# cc2538-dev-v1.net
KiCad netlist of a schematic drawn in EAGLE
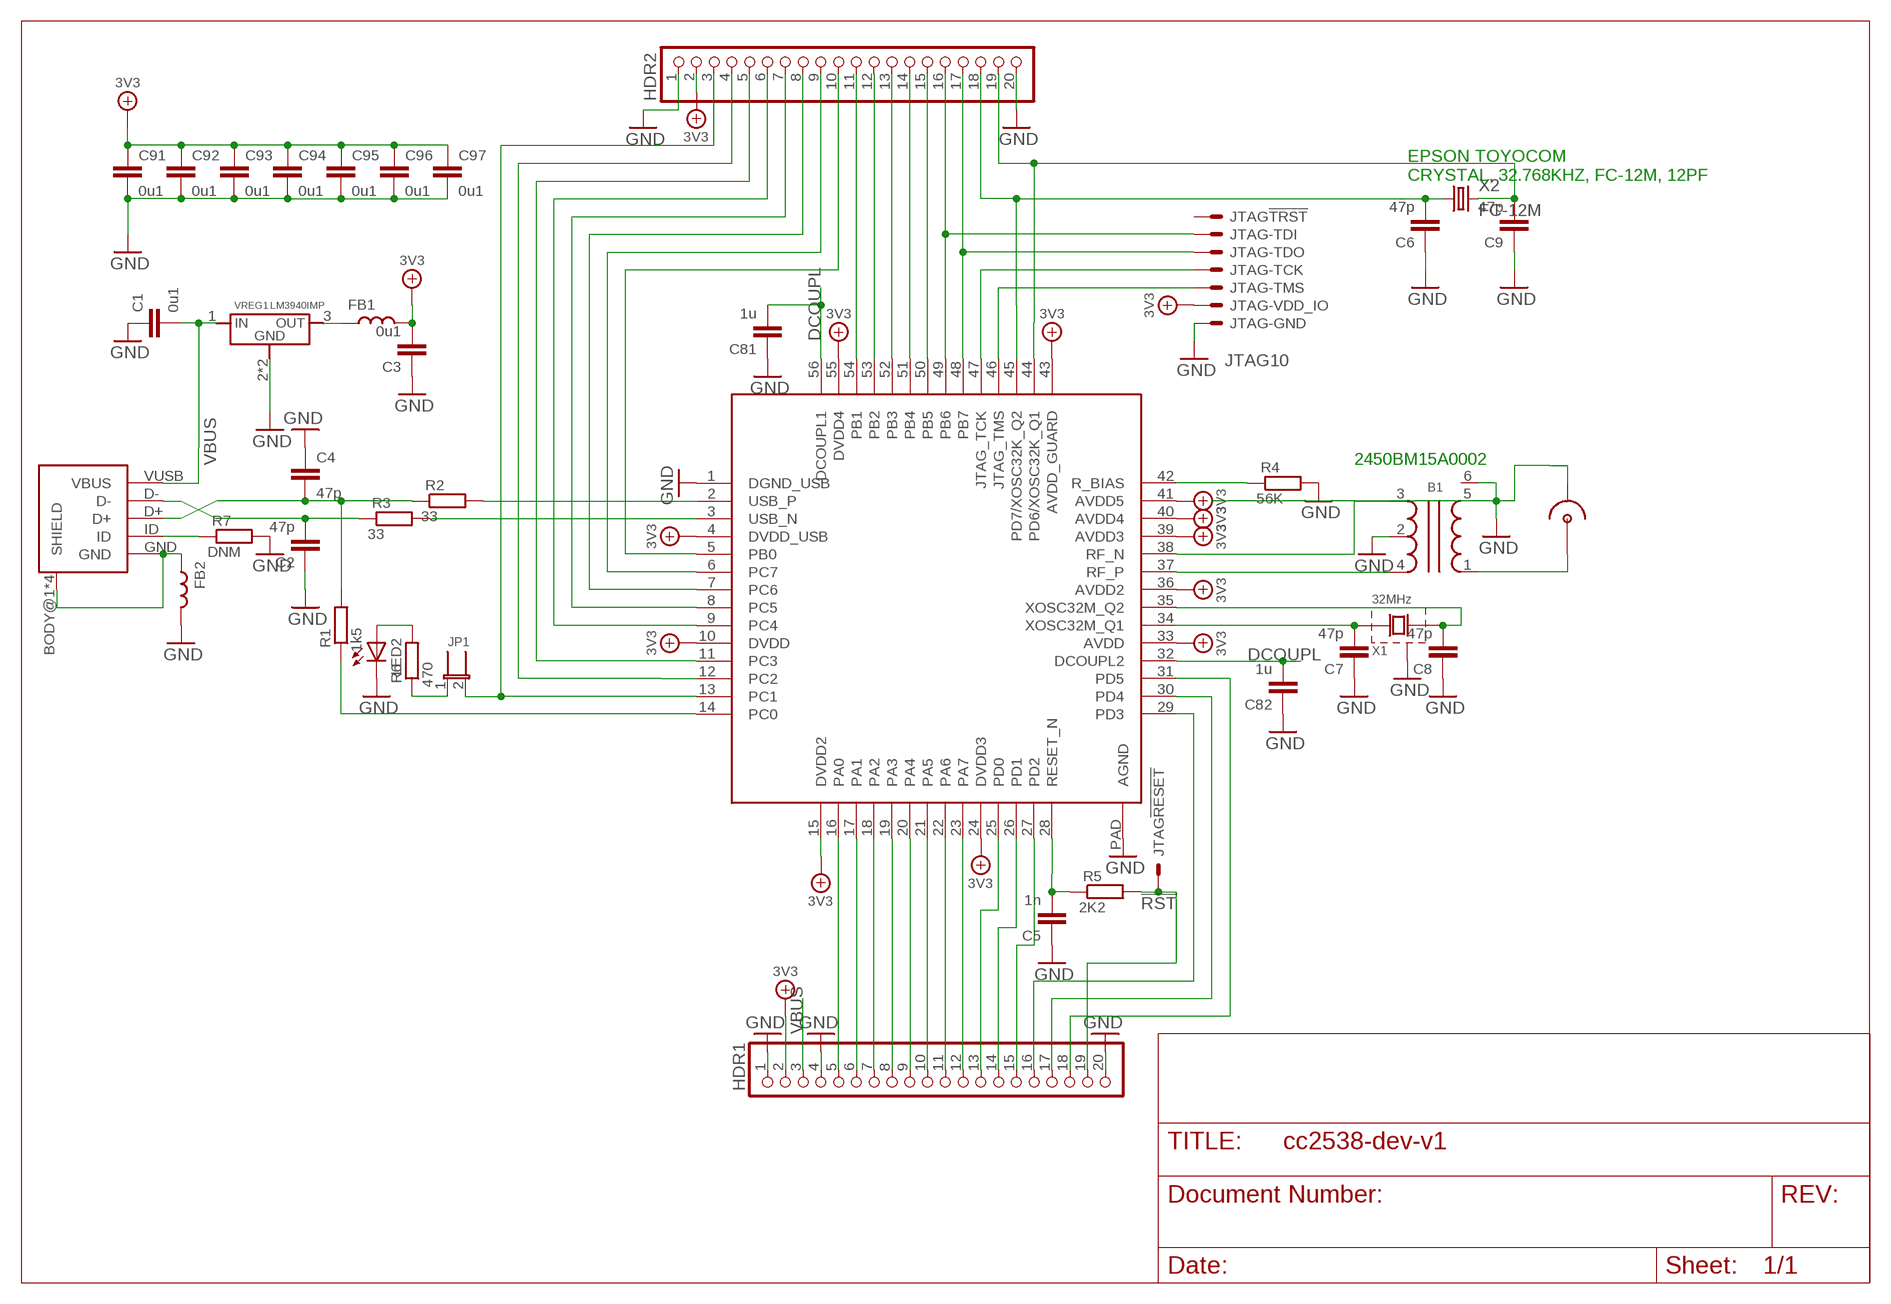
[diagram p0: schematic, sheet 1]

(export (version "E")
  (design (tool "Eeschema 10.0.6"))
  (components
    (comp (ref "B1")
      (value "BALUN")
      (footprint "eagle-import:BALUN-0805")
      (libsource (lib "eagle-import") (part "BALUN"))
    )
    (comp (ref "C1")
      (value "0u1")
      (footprint "eagle-import:C1206")
      (libsource (lib "eagle-import") (part "CC1206"))
    )
    (comp (ref "C2")
      (value "47p")
      (footprint "eagle-import:C0603")
      (libsource (lib "eagle-import") (part "CC0603"))
    )
    (comp (ref "C3")
      (value "0u1")
      (footprint "eagle-import:C1206")
      (libsource (lib "eagle-import") (part "CC1206"))
    )
    (comp (ref "C4")
      (value "47p")
      (footprint "eagle-import:C0603")
      (libsource (lib "eagle-import") (part "CC0603"))
    )
    (comp (ref "C5")
      (value "1n")
      (footprint "eagle-import:C0603")
      (libsource (lib "eagle-import") (part "CC0603"))
    )
    (comp (ref "C6")
      (value "47p")
      (footprint "eagle-import:C0603")
      (libsource (lib "eagle-import") (part "CC0603"))
    )
    (comp (ref "C7")
      (value "47p")
      (footprint "eagle-import:C0603")
      (libsource (lib "eagle-import") (part "CC0603"))
    )
    (comp (ref "C8")
      (value "47p")
      (footprint "eagle-import:C0603")
      (libsource (lib "eagle-import") (part "CC0603"))
    )
    (comp (ref "C9")
      (value "47p")
      (footprint "eagle-import:C0603")
      (libsource (lib "eagle-import") (part "CC0603"))
    )
    (comp (ref "C81")
      (value "1u")
      (footprint "eagle-import:C0402")
      (libsource (lib "eagle-import") (part "CC0402"))
    )
    (comp (ref "C82")
      (value "1u")
      (footprint "eagle-import:C0402")
      (libsource (lib "eagle-import") (part "CC0402"))
    )
    (comp (ref "C91")
      (value "0u1")
      (footprint "eagle-import:C0402")
      (libsource (lib "eagle-import") (part "CC0402"))
    )
    (comp (ref "C92")
      (value "0u1")
      (footprint "eagle-import:C0402")
      (libsource (lib "eagle-import") (part "CC0402"))
    )
    (comp (ref "C93")
      (value "0u1")
      (footprint "eagle-import:C0402")
      (libsource (lib "eagle-import") (part "CC0402"))
    )
    (comp (ref "C94")
      (value "0u1")
      (footprint "eagle-import:C0402")
      (libsource (lib "eagle-import") (part "CC0402"))
    )
    (comp (ref "C95")
      (value "0u1")
      (footprint "eagle-import:C0402")
      (libsource (lib "eagle-import") (part "CC0402"))
    )
    (comp (ref "C96")
      (value "0u1")
      (footprint "eagle-import:C0402")
      (libsource (lib "eagle-import") (part "CC0402"))
    )
    (comp (ref "C97")
      (value "0u1")
      (footprint "eagle-import:C0402")
      (libsource (lib "eagle-import") (part "CC0402"))
    )
    (comp (ref "CN1")
      (value "USB-OTG")
      (footprint "eagle-import:CONN_USB_MINI-B")
      (libsource (lib "eagle-import") (part "USB-OTG"))
    )
    (comp (ref "CN2")
      (value "RF-CONNSMA")
      (footprint "eagle-import:SMA")
      (libsource (lib "eagle-import") (part "RF-CONNSMA"))
    )
    (comp (ref "FB1")
      (value "L0603")
      (footprint "eagle-import:R603")
      (libsource (lib "eagle-import") (part "L0603"))
    )
    (comp (ref "FB2")
      (value "L0603")
      (footprint "eagle-import:R603")
      (libsource (lib "eagle-import") (part "L0603"))
    )
    (comp (ref "HDR1")
      (value "PINHD-1X20")
      (footprint "eagle-import:1X20")
      (libsource (lib "eagle-import") (part "PINHD-1X20"))
    )
    (comp (ref "HDR2")
      (value "PINHD-1X20")
      (footprint "eagle-import:1X20")
      (libsource (lib "eagle-import") (part "PINHD-1X20"))
    )
    (comp (ref "JP1")
      (value "JP-2MM-2")
      (footprint "eagle-import:JP-2MM-2")
      (libsource (lib "eagle-import") (part "JP-2MM-2"))
    )
    (comp (ref "JTAG")
      (value "JTAG10")
      (footprint "eagle-import:HDR-2X5-2.00")
      (libsource (lib "eagle-import") (part "JTAG10"))
    )
    (comp (ref "LED2")
      (value "LED805")
      (footprint "eagle-import:LED-805")
      (libsource (lib "eagle-import") (part "LED805"))
    )
    (comp (ref "R1")
      (value "1k5")
      (footprint "eagle-import:R603")
      (libsource (lib "eagle-import") (part "RR603"))
    )
    (comp (ref "R2")
      (value "33")
      (footprint "eagle-import:R603")
      (libsource (lib "eagle-import") (part "RR603"))
    )
    (comp (ref "R3")
      (value "33")
      (footprint "eagle-import:R603")
      (libsource (lib "eagle-import") (part "RR603"))
    )
    (comp (ref "R4")
      (value "56K")
      (footprint "eagle-import:R603")
      (libsource (lib "eagle-import") (part "RR603"))
    )
    (comp (ref "R5")
      (value "2K2")
      (footprint "eagle-import:R603")
      (libsource (lib "eagle-import") (part "RR603"))
    )
    (comp (ref "R6")
      (value "470")
      (footprint "eagle-import:R603")
      (libsource (lib "eagle-import") (part "RR603"))
    )
    (comp (ref "R7")
      (value "DNM")
      (footprint "eagle-import:R603")
      (libsource (lib "eagle-import") (part "RR603"))
    )
    (comp (ref "U1")
      (value "CC2538")
      (footprint "eagle-import:QFN56")
      (libsource (lib "eagle-import") (part "CC2538"))
    )
    (comp (ref "VREG1")
      (value "LM3940IMP")
      (footprint "eagle-import:SOT223")
      (libsource (lib "eagle-import") (part "LM3940IMP"))
    )
    (comp (ref "X1")
      (value "32MHz")
      (footprint "eagle-import:XTAL-4-3225")
      (libsource (lib "eagle-import") (part "XTAL-43225"))
    )
    (comp (ref "X2")
      (value "FC-12M")
      (footprint "eagle-import:FC-12M")
      (libsource (lib "eagle-import") (part "FC-12M"))
    )
  )
  (nets
    (net (code "1") (name "/DCOUPL") (class "Default")
      (node (ref "C81") (pin "2") (pinfunction "2_2") (pintype "passive"))
      (node (ref "C82") (pin "2") (pinfunction "2_2") (pintype "passive"))
      (node (ref "U1") (pin "32") (pinfunction "DCOUPL2_32") (pintype "bidirectional"))
      (node (ref "U1") (pin "56") (pinfunction "DCOUPL1_56") (pintype "bidirectional"))
    )
    (net (code "2") (name "/VBUS") (class "Default")
      (node (ref "C1") (pin "2") (pinfunction "2_2") (pintype "passive"))
      (node (ref "CN1") (pin "VUSB") (pinfunction "VBUS_VUSB") (pintype "bidirectional"))
      (node (ref "HDR1") (pin "3") (pinfunction "3_3") (pintype "passive"))
      (node (ref "VREG1") (pin "1") (pinfunction "IN_1") (pintype "bidirectional"))
    )
    (net (code "3") (name "/~{RST}") (class "Default")
      (node (ref "HDR1") (pin "19") (pinfunction "19_19") (pintype "passive"))
      (node (ref "JTAG") (pin "4") (pinfunction "S_4") (pintype "passive"))
      (node (ref "R5") (pin "2") (pinfunction "2_2") (pintype "passive"))
    )
    (net (code "4") (name "3V3") (class "Default")
      (node (ref "C3") (pin "2") (pinfunction "2_2") (pintype "passive"))
      (node (ref "C91") (pin "1") (pinfunction "1_1") (pintype "passive"))
      (node (ref "C92") (pin "1") (pinfunction "1_1") (pintype "passive"))
      (node (ref "C93") (pin "1") (pinfunction "1_1") (pintype "passive"))
      (node (ref "C94") (pin "1") (pinfunction "1_1") (pintype "passive"))
      (node (ref "C95") (pin "1") (pinfunction "1_1") (pintype "passive"))
      (node (ref "C96") (pin "1") (pinfunction "1_1") (pintype "passive"))
      (node (ref "C97") (pin "1") (pinfunction "1_1") (pintype "passive"))
      (node (ref "FB1") (pin "2") (pinfunction "P$2_2") (pintype "bidirectional"))
      (node (ref "HDR1") (pin "2") (pinfunction "2_2") (pintype "passive"))
      (node (ref "HDR2") (pin "2") (pinfunction "2_2") (pintype "passive"))
      (node (ref "JTAG") (pin "1") (pinfunction "S_1") (pintype "passive"))
      (node (ref "JTAG") (pin "2") (pinfunction "S_2") (pintype "passive"))
      (node (ref "U1") (pin "10") (pinfunction "DVDD_10") (pintype "bidirectional"))
      (node (ref "U1") (pin "15") (pinfunction "DVDD2_15") (pintype "bidirectional"))
      (node (ref "U1") (pin "24") (pinfunction "DVDD3_24") (pintype "bidirectional"))
      (node (ref "U1") (pin "33") (pinfunction "AVDD_33") (pintype "bidirectional"))
      (node (ref "U1") (pin "36") (pinfunction "AVDD2_36") (pintype "bidirectional"))
      (node (ref "U1") (pin "39") (pinfunction "AVDD3_39") (pintype "bidirectional"))
      (node (ref "U1") (pin "4") (pinfunction "DVDD_USB_4") (pintype "bidirectional"))
      (node (ref "U1") (pin "40") (pinfunction "AVDD4_40") (pintype "bidirectional"))
      (node (ref "U1") (pin "41") (pinfunction "AVDD5_41") (pintype "bidirectional"))
      (node (ref "U1") (pin "43") (pinfunction "AVDD_GUARD_43") (pintype "bidirectional"))
      (node (ref "U1") (pin "55") (pinfunction "DVDD4_55") (pintype "bidirectional"))
    )
    (net (code "5") (name "GND") (class "Default")
      (node (ref "B1") (pin "2") (pinfunction "2_2") (pintype "bidirectional"))
      (node (ref "B1") (pin "5") (pinfunction "5_5") (pintype "bidirectional"))
      (node (ref "B1") (pin "6") (pinfunction "6_6") (pintype "bidirectional"))
      (node (ref "C1") (pin "1") (pinfunction "1_1") (pintype "passive"))
      (node (ref "C2") (pin "1") (pinfunction "1_1") (pintype "passive"))
      (node (ref "C3") (pin "1") (pinfunction "1_1") (pintype "passive"))
      (node (ref "C4") (pin "1") (pinfunction "1_1") (pintype "passive"))
      (node (ref "C5") (pin "1") (pinfunction "1_1") (pintype "passive"))
      (node (ref "C6") (pin "1") (pinfunction "1_1") (pintype "passive"))
      (node (ref "C7") (pin "1") (pinfunction "1_1") (pintype "passive"))
      (node (ref "C8") (pin "1") (pinfunction "1_1") (pintype "passive"))
      (node (ref "C81") (pin "1") (pinfunction "1_1") (pintype "passive"))
      (node (ref "C82") (pin "1") (pinfunction "1_1") (pintype "passive"))
      (node (ref "C9") (pin "1") (pinfunction "1_1") (pintype "passive"))
      (node (ref "C91") (pin "2") (pinfunction "2_2") (pintype "passive"))
      (node (ref "C92") (pin "2") (pinfunction "2_2") (pintype "passive"))
      (node (ref "C93") (pin "2") (pinfunction "2_2") (pintype "passive"))
      (node (ref "C94") (pin "2") (pinfunction "2_2") (pintype "passive"))
      (node (ref "C95") (pin "2") (pinfunction "2_2") (pintype "passive"))
      (node (ref "C96") (pin "2") (pinfunction "2_2") (pintype "passive"))
      (node (ref "C97") (pin "2") (pinfunction "2_2") (pintype "passive"))
      (node (ref "CN2") (pin "GND1") (pinfunction "GND_GND1") (pintype "bidirectional"))
      (node (ref "CN2") (pin "GND2") (pinfunction "GND_GND2") (pintype "bidirectional"))
      (node (ref "CN2") (pin "GND3") (pinfunction "GND_GND3") (pintype "bidirectional"))
      (node (ref "CN2") (pin "GND4") (pinfunction "GND_GND4") (pintype "bidirectional"))
      (node (ref "FB2") (pin "2") (pinfunction "P$2_2") (pintype "bidirectional"))
      (node (ref "HDR1") (pin "1") (pinfunction "1_1") (pintype "passive"))
      (node (ref "HDR1") (pin "20") (pinfunction "20_20") (pintype "passive"))
      (node (ref "HDR1") (pin "4") (pinfunction "4_4") (pintype "passive"))
      (node (ref "HDR2") (pin "1") (pinfunction "1_1") (pintype "passive"))
      (node (ref "HDR2") (pin "20") (pinfunction "20_20") (pintype "passive"))
      (node (ref "JTAG") (pin "10") (pinfunction "S_10") (pintype "passive"))
      (node (ref "JTAG") (pin "8") (pinfunction "S_8") (pintype "passive"))
      (node (ref "LED2") (pin "C") (pinfunction "C_C") (pintype "passive"))
      (node (ref "R4") (pin "2") (pinfunction "2_2") (pintype "passive"))
      (node (ref "R7") (pin "2") (pinfunction "2_2") (pintype "passive"))
      (node (ref "U1") (pin "1") (pinfunction "DGND_USB_1") (pintype "bidirectional"))
      (node (ref "U1") (pin "PAD") (pinfunction "AGND_PAD") (pintype "bidirectional"))
      (node (ref "VREG1") (pin "2") (pinfunction "GND_2") (pintype "bidirectional"))
      (node (ref "VREG1") (pin "4") (pinfunction "GND_4") (pintype "bidirectional"))
      (node (ref "X1") (pin "2") (pinfunction "GND1_2") (pintype "bidirectional"))
      (node (ref "X1") (pin "4") (pinfunction "GND1_4") (pintype "bidirectional"))
    )
    (net (code "6") (name "Net-(C2-Pad2)") (class "Default")
      (node (ref "C2") (pin "2") (pinfunction "2_2") (pintype "passive"))
      (node (ref "CN1") (pin "D-") (pinfunction "D-_D-") (pintype "bidirectional"))
      (node (ref "R3") (pin "1") (pinfunction "1_1") (pintype "passive"))
    )
    (net (code "7") (name "Net-(C4-Pad2)") (class "Default")
      (node (ref "C4") (pin "2") (pinfunction "2_2") (pintype "passive"))
      (node (ref "CN1") (pin "D+") (pinfunction "D+_D+") (pintype "bidirectional"))
      (node (ref "R1") (pin "2") (pinfunction "2_2") (pintype "passive"))
      (node (ref "R2") (pin "1") (pinfunction "1_1") (pintype "passive"))
    )
    (net (code "8") (name "Net-(CN1-PadID)") (class "Default")
      (node (ref "CN1") (pin "ID") (pinfunction "ID_ID") (pintype "bidirectional"))
      (node (ref "R7") (pin "1") (pinfunction "1_1") (pintype "passive"))
    )
    (net (code "9") (name "Net-(CN2-SIGNAL)") (class "Default")
      (node (ref "B1") (pin "1") (pinfunction "1_1") (pintype "bidirectional"))
      (node (ref "CN2") (pin "SIG") (pinfunction "SIGNAL_SIG") (pintype "bidirectional"))
    )
    (net (code "10") (name "Net-(FB1-P$1)") (class "Default")
      (node (ref "FB1") (pin "1") (pinfunction "P$1_1") (pintype "bidirectional"))
      (node (ref "VREG1") (pin "3") (pinfunction "OUT_3") (pintype "bidirectional"))
    )
    (net (code "11") (name "Net-(FB2-P$1)") (class "Default")
      (node (ref "CN1") (pin "BODY@1") (pinfunction "SHIELD_BODY@1") (pintype "bidirectional"))
      (node (ref "CN1") (pin "BODY@2") (pinfunction "SHIELD_BODY@2") (pintype "bidirectional"))
      (node (ref "CN1") (pin "BODY@3") (pinfunction "SHIELD_BODY@3") (pintype "bidirectional"))
      (node (ref "CN1") (pin "BODY@4") (pinfunction "SHIELD_BODY@4") (pintype "bidirectional"))
      (node (ref "CN1") (pin "GND") (pinfunction "GND_GND") (pintype "bidirectional"))
      (node (ref "FB2") (pin "1") (pinfunction "P$1_1") (pintype "bidirectional"))
    )
    (net (code "12") (name "Net-(JP1-Pad1)") (class "Default")
      (node (ref "JP1") (pin "1") (pinfunction "1_1") (pintype "bidirectional"))
      (node (ref "R6") (pin "1") (pinfunction "1_1") (pintype "passive"))
    )
    (net (code "13") (name "Net-(JTAGD-S)") (class "Default")
      (node (ref "JTAG") (pin "9") (pinfunction "S_9") (pintype "passive"))
      (node (ref "U1") (pin "47") (pinfunction "JTAG_TCK_47") (pintype "bidirectional"))
    )
    (net (code "14") (name "Net-(JTAGE-S)") (class "Default")
      (node (ref "HDR2") (pin "16") (pinfunction "16_16") (pintype "passive"))
      (node (ref "JTAG") (pin "5") (pinfunction "S_5") (pintype "passive"))
      (node (ref "U1") (pin "49") (pinfunction "PB6_49") (pintype "bidirectional"))
    )
    (net (code "15") (name "Net-(JTAGF-S)") (class "Default")
      (node (ref "HDR2") (pin "17") (pinfunction "17_17") (pintype "passive"))
      (node (ref "JTAG") (pin "6") (pinfunction "S_6") (pintype "passive"))
      (node (ref "U1") (pin "48") (pinfunction "PB7_48") (pintype "bidirectional"))
    )
    (net (code "16") (name "Net-(JTAGG-S)") (class "Default")
      (node (ref "JTAG") (pin "7") (pinfunction "S_7") (pintype "passive"))
      (node (ref "U1") (pin "46") (pinfunction "JTAG_TMS_46") (pintype "bidirectional"))
    )
    (net (code "17") (name "Net-(LED2-PadA)") (class "Default")
      (node (ref "LED2") (pin "A") (pinfunction "A_A") (pintype "passive"))
      (node (ref "R6") (pin "2") (pinfunction "2_2") (pintype "passive"))
    )
    (net (code "18") (name "Net-(U1-PA0)") (class "Default")
      (node (ref "HDR1") (pin "5") (pinfunction "5_5") (pintype "passive"))
      (node (ref "U1") (pin "16") (pinfunction "PA0_16") (pintype "bidirectional"))
    )
    (net (code "19") (name "Net-(U1-PA1)") (class "Default")
      (node (ref "HDR1") (pin "6") (pinfunction "6_6") (pintype "passive"))
      (node (ref "U1") (pin "17") (pinfunction "PA1_17") (pintype "bidirectional"))
    )
    (net (code "20") (name "Net-(U1-PA2)") (class "Default")
      (node (ref "HDR1") (pin "7") (pinfunction "7_7") (pintype "passive"))
      (node (ref "U1") (pin "18") (pinfunction "PA2_18") (pintype "bidirectional"))
    )
    (net (code "21") (name "Net-(U1-PA3)") (class "Default")
      (node (ref "HDR1") (pin "8") (pinfunction "8_8") (pintype "passive"))
      (node (ref "U1") (pin "19") (pinfunction "PA3_19") (pintype "bidirectional"))
    )
    (net (code "22") (name "Net-(U1-PA4)") (class "Default")
      (node (ref "HDR1") (pin "9") (pinfunction "9_9") (pintype "passive"))
      (node (ref "U1") (pin "20") (pinfunction "PA4_20") (pintype "bidirectional"))
    )
    (net (code "23") (name "Net-(U1-PA5)") (class "Default")
      (node (ref "HDR1") (pin "10") (pinfunction "10_10") (pintype "passive"))
      (node (ref "U1") (pin "21") (pinfunction "PA5_21") (pintype "bidirectional"))
    )
    (net (code "24") (name "Net-(U1-PA6)") (class "Default")
      (node (ref "HDR1") (pin "11") (pinfunction "11_11") (pintype "passive"))
      (node (ref "U1") (pin "22") (pinfunction "PA6_22") (pintype "bidirectional"))
    )
    (net (code "25") (name "Net-(U1-PA7)") (class "Default")
      (node (ref "HDR1") (pin "12") (pinfunction "12_12") (pintype "passive"))
      (node (ref "U1") (pin "23") (pinfunction "PA7_23") (pintype "bidirectional"))
    )
    (net (code "26") (name "Net-(U1-PB0)") (class "Default")
      (node (ref "HDR2") (pin "10") (pinfunction "10_10") (pintype "passive"))
      (node (ref "U1") (pin "5") (pinfunction "PB0_5") (pintype "bidirectional"))
    )
    (net (code "27") (name "Net-(U1-PB1)") (class "Default")
      (node (ref "HDR2") (pin "11") (pinfunction "11_11") (pintype "passive"))
      (node (ref "U1") (pin "54") (pinfunction "PB1_54") (pintype "bidirectional"))
    )
    (net (code "28") (name "Net-(U1-PB2)") (class "Default")
      (node (ref "HDR2") (pin "12") (pinfunction "12_12") (pintype "passive"))
      (node (ref "U1") (pin "53") (pinfunction "PB2_53") (pintype "bidirectional"))
    )
    (net (code "29") (name "Net-(U1-PB3)") (class "Default")
      (node (ref "HDR2") (pin "13") (pinfunction "13_13") (pintype "passive"))
      (node (ref "U1") (pin "52") (pinfunction "PB3_52") (pintype "bidirectional"))
    )
    (net (code "30") (name "Net-(U1-PB4)") (class "Default")
      (node (ref "HDR2") (pin "14") (pinfunction "14_14") (pintype "passive"))
      (node (ref "U1") (pin "51") (pinfunction "PB4_51") (pintype "bidirectional"))
    )
    (net (code "31") (name "Net-(U1-PB5)") (class "Default")
      (node (ref "HDR2") (pin "15") (pinfunction "15_15") (pintype "passive"))
      (node (ref "U1") (pin "50") (pinfunction "PB5_50") (pintype "bidirectional"))
    )
    (net (code "32") (name "Net-(U1-PC0)") (class "Default")
      (node (ref "R1") (pin "1") (pinfunction "1_1") (pintype "passive"))
      (node (ref "U1") (pin "14") (pinfunction "PC0_14") (pintype "bidirectional"))
    )
    (net (code "33") (name "Net-(U1-PC1)") (class "Default")
      (node (ref "HDR2") (pin "3") (pinfunction "3_3") (pintype "passive"))
      (node (ref "JP1") (pin "2") (pinfunction "2_2") (pintype "bidirectional"))
      (node (ref "U1") (pin "13") (pinfunction "PC1_13") (pintype "bidirectional"))
    )
    (net (code "34") (name "Net-(U1-PC2)") (class "Default")
      (node (ref "HDR2") (pin "4") (pinfunction "4_4") (pintype "passive"))
      (node (ref "U1") (pin "12") (pinfunction "PC2_12") (pintype "bidirectional"))
    )
    (net (code "35") (name "Net-(U1-PC3)") (class "Default")
      (node (ref "HDR2") (pin "5") (pinfunction "5_5") (pintype "passive"))
      (node (ref "U1") (pin "11") (pinfunction "PC3_11") (pintype "bidirectional"))
    )
    (net (code "36") (name "Net-(U1-PC4)") (class "Default")
      (node (ref "HDR2") (pin "6") (pinfunction "6_6") (pintype "passive"))
      (node (ref "U1") (pin "9") (pinfunction "PC4_9") (pintype "bidirectional"))
    )
    (net (code "37") (name "Net-(U1-PC5)") (class "Default")
      (node (ref "HDR2") (pin "7") (pinfunction "7_7") (pintype "passive"))
      (node (ref "U1") (pin "8") (pinfunction "PC5_8") (pintype "bidirectional"))
    )
    (net (code "38") (name "Net-(U1-PC6)") (class "Default")
      (node (ref "HDR2") (pin "8") (pinfunction "8_8") (pintype "passive"))
      (node (ref "U1") (pin "7") (pinfunction "PC6_7") (pintype "bidirectional"))
    )
    (net (code "39") (name "Net-(U1-PC7)") (class "Default")
      (node (ref "HDR2") (pin "9") (pinfunction "9_9") (pintype "passive"))
      (node (ref "U1") (pin "6") (pinfunction "PC7_6") (pintype "bidirectional"))
    )
    (net (code "40") (name "Net-(U1-PD0)") (class "Default")
      (node (ref "HDR1") (pin "13") (pinfunction "13_13") (pintype "passive"))
      (node (ref "U1") (pin "25") (pinfunction "PD0_25") (pintype "bidirectional"))
    )
    (net (code "41") (name "Net-(U1-PD1)") (class "Default")
      (node (ref "HDR1") (pin "14") (pinfunction "14_14") (pintype "passive"))
      (node (ref "U1") (pin "26") (pinfunction "PD1_26") (pintype "bidirectional"))
    )
    (net (code "42") (name "Net-(U1-PD2)") (class "Default")
      (node (ref "HDR1") (pin "15") (pinfunction "15_15") (pintype "passive"))
      (node (ref "U1") (pin "27") (pinfunction "PD2_27") (pintype "bidirectional"))
    )
    (net (code "43") (name "Net-(U1-PD3)") (class "Default")
      (node (ref "HDR1") (pin "16") (pinfunction "16_16") (pintype "passive"))
      (node (ref "U1") (pin "29") (pinfunction "PD3_29") (pintype "bidirectional"))
    )
    (net (code "44") (name "Net-(U1-PD4)") (class "Default")
      (node (ref "HDR1") (pin "17") (pinfunction "17_17") (pintype "passive"))
      (node (ref "U1") (pin "30") (pinfunction "PD4_30") (pintype "bidirectional"))
    )
    (net (code "45") (name "Net-(U1-PD5)") (class "Default")
      (node (ref "HDR1") (pin "18") (pinfunction "18_18") (pintype "passive"))
      (node (ref "U1") (pin "31") (pinfunction "PD5_31") (pintype "bidirectional"))
    )
    (net (code "46") (name "Net-(U1-PD6{slash}XOSC32K_Q1)") (class "Default")
      (node (ref "C9") (pin "2") (pinfunction "2_2") (pintype "passive"))
      (node (ref "HDR2") (pin "19") (pinfunction "19_19") (pintype "passive"))
      (node (ref "U1") (pin "44") (pinfunction "PD6/XOSC32K_Q1_44") (pintype "bidirectional"))
      (node (ref "X2") (pin "2") (pinfunction "2_2") (pintype "passive"))
    )
    (net (code "47") (name "Net-(U1-PD7{slash}XOSC32K_Q2)") (class "Default")
      (node (ref "C6") (pin "2") (pinfunction "2_2") (pintype "passive"))
      (node (ref "HDR2") (pin "18") (pinfunction "18_18") (pintype "passive"))
      (node (ref "U1") (pin "45") (pinfunction "PD7/XOSC32K_Q2_45") (pintype "bidirectional"))
      (node (ref "X2") (pin "1") (pinfunction "1_1") (pintype "passive"))
    )
    (net (code "48") (name "Net-(U1-RESET_N)") (class "Default")
      (node (ref "C5") (pin "2") (pinfunction "2_2") (pintype "passive"))
      (node (ref "R5") (pin "1") (pinfunction "1_1") (pintype "passive"))
      (node (ref "U1") (pin "28") (pinfunction "RESET_N_28") (pintype "bidirectional"))
    )
    (net (code "49") (name "Net-(U1-RF_N)") (class "Default")
      (node (ref "B1") (pin "3") (pinfunction "3_3") (pintype "bidirectional"))
      (node (ref "U1") (pin "38") (pinfunction "RF_N_38") (pintype "bidirectional"))
    )
    (net (code "50") (name "Net-(U1-RF_P)") (class "Default")
      (node (ref "B1") (pin "4") (pinfunction "4_4") (pintype "bidirectional"))
      (node (ref "U1") (pin "37") (pinfunction "RF_P_37") (pintype "bidirectional"))
    )
    (net (code "51") (name "Net-(U1-R_BIAS)") (class "Default")
      (node (ref "R4") (pin "1") (pinfunction "1_1") (pintype "passive"))
      (node (ref "U1") (pin "42") (pinfunction "R_BIAS_42") (pintype "bidirectional"))
    )
    (net (code "52") (name "Net-(U1-USB_N)") (class "Default")
      (node (ref "R3") (pin "2") (pinfunction "2_2") (pintype "passive"))
      (node (ref "U1") (pin "3") (pinfunction "USB_N_3") (pintype "bidirectional"))
    )
    (net (code "53") (name "Net-(U1-USB_P)") (class "Default")
      (node (ref "R2") (pin "2") (pinfunction "2_2") (pintype "passive"))
      (node (ref "U1") (pin "2") (pinfunction "USB_P_2") (pintype "bidirectional"))
    )
    (net (code "54") (name "Net-(U1-XOSC32M_Q1)") (class "Default")
      (node (ref "C7") (pin "2") (pinfunction "2_2") (pintype "passive"))
      (node (ref "U1") (pin "34") (pinfunction "XOSC32M_Q1_34") (pintype "bidirectional"))
      (node (ref "X1") (pin "1") (pinfunction "X1_1") (pintype "bidirectional"))
    )
    (net (code "55") (name "Net-(U1-XOSC32M_Q2)") (class "Default")
      (node (ref "C8") (pin "2") (pinfunction "2_2") (pintype "passive"))
      (node (ref "U1") (pin "35") (pinfunction "XOSC32M_Q2_35") (pintype "bidirectional"))
      (node (ref "X1") (pin "3") (pinfunction "X2_3") (pintype "bidirectional"))
    )
    (net (code "56") (name "unconnected-(JTAGB-S-Pad3)") (class "Default")
      (node (ref "JTAG") (pin "3") (pinfunction "S_3") (pintype "passive"))
    )
  )
)
